# 02_Arduino_Headers.net
KiCad netlist of a schematic drawn in Altium Designer
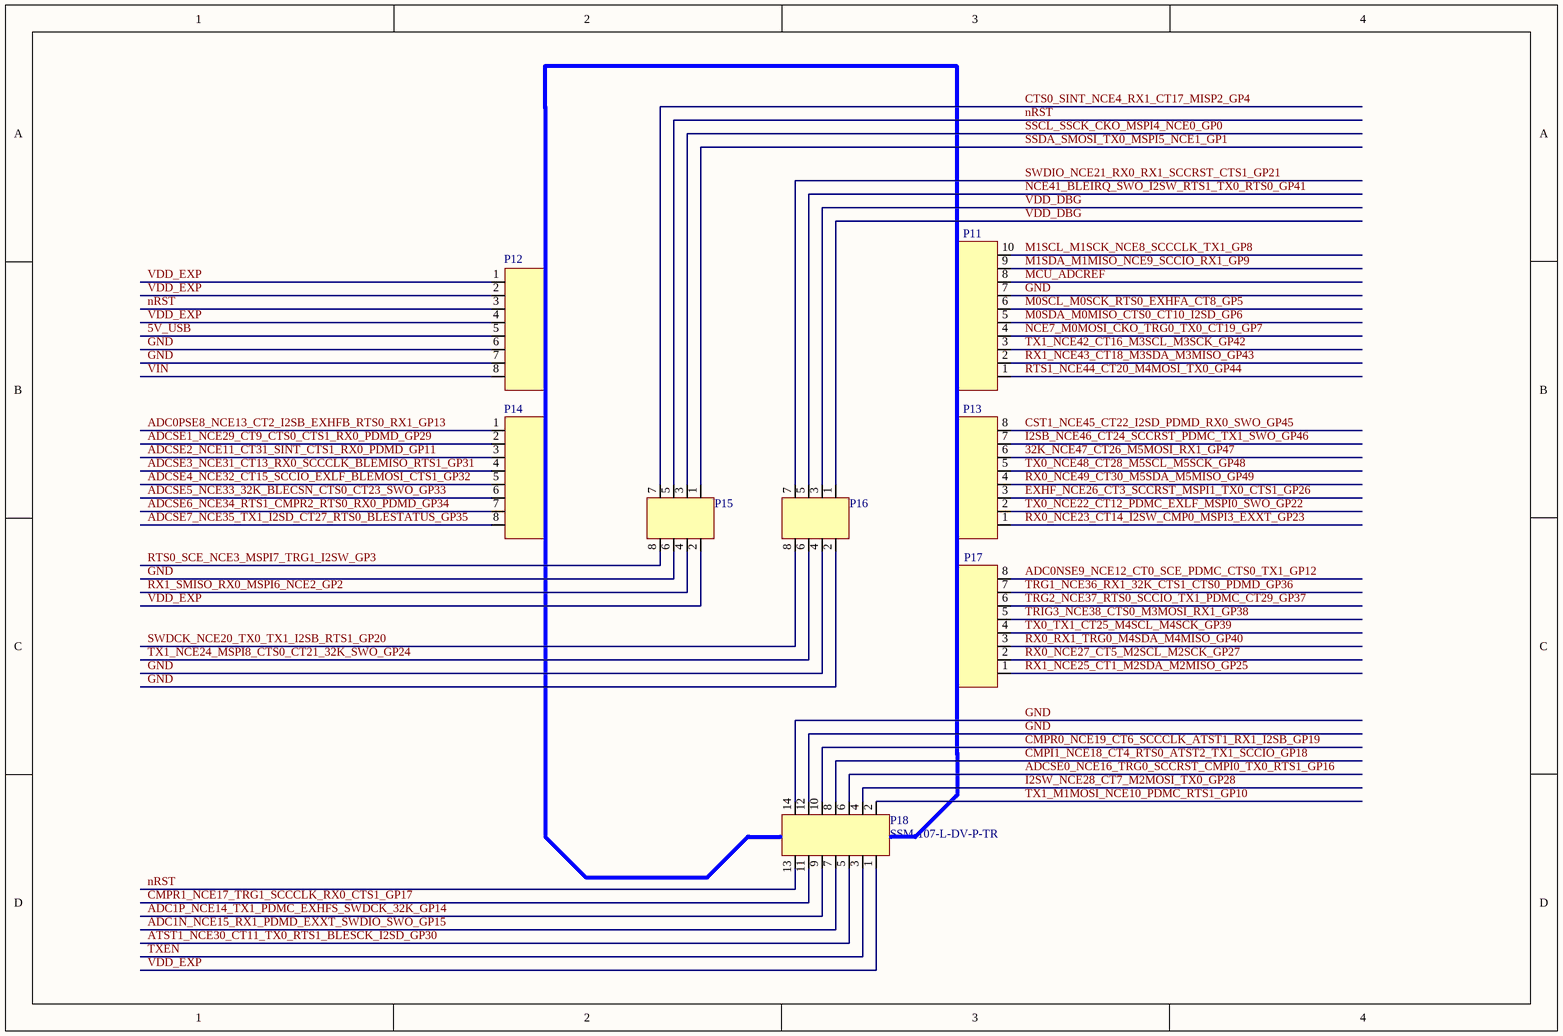
[diagram p0: [02]Arduino Headers.SchDoc]

(export (version "E")
  (design (tool "Eeschema 10.0.6"))
  (components
    (comp (ref "P11")
      (value "SSM-110-L-SV-P-TR")
      (footprint "SSM-110-L-SV-TR")
      (description "10 Position Receptacle, Pass Through Connector 2.54mm Gold SMD")
      (libsource (lib "Connector") (part "SSM-110-L-SV-P-TR"))
    )
    (comp (ref "P12")
      (value "SSM-108-L-SV-P-TR")
      (footprint "SSM-108-L-SV-TR")
      (description "8 Position Receptacle, Pass Through Connector 2.54mm Gold SMD")
      (libsource (lib "") (part "SSM-108-L-SV-P-TR_1"))
    )
    (comp (ref "P13")
      (value "SSM-108-L-SV-P-TR")
      (footprint "SSM-108-L-SV-TR")
      (description "8 Position Receptacle, Pass Through Connector 2.54mm Gold SMD")
      (libsource (lib "Connector") (part "SSM-108-L-SV-P-TR"))
    )
    (comp (ref "P14")
      (value "SSM-108-L-SV-P-TR")
      (footprint "SSM-108-L-SV-TR")
      (description "8 Position Receptacle, Pass Through Connector 2.54mm Gold SMD")
      (libsource (lib "") (part "SSM-108-L-SV-P-TR_1"))
    )
    (comp (ref "P15")
      (value "TSM-104-04-F-DV-P-TR")
      (footprint "TSM-104-04-F-DV-TR")
      (description "8 Positions Header, 2 Row,Gold, Unshrouded Connector 2.54mm SMD")
      (libsource (lib "Connector") (part "TSM-104-04-F-DV-P-TR"))
    )
    (comp (ref "P16")
      (value "TSM-104-04-F-DV-P-TR")
      (footprint "TSM-104-04-F-DV-TR")
      (description "8 Positions Header, 2 Row,Gold, Unshrouded Connector 2.54mm SMD")
      (libsource (lib "Connector") (part "TSM-104-04-F-DV-P-TR"))
    )
    (comp (ref "P17")
      (value "SSM-108-L-SV-P-TR")
      (footprint "SSM-108-L-SV-TR")
      (description "8 Position Receptacle, Pass Through Connector 2.54mm Gold SMD")
      (libsource (lib "Connector") (part "SSM-108-L-SV-P-TR"))
    )
    (comp (ref "P18")
      (value "SSM-107-L-DV-P-TR")
      (footprint "SSM-107-L-DV-TR")
      (description "14 Positions Socket Strip, Double Row Vertical 2,54mm SMD")
      (libsource (lib "Connector") (part "SSM-107-L-DV-P-TR"))
    )
  )
  (nets
    (net (code "1") (name "/5V_USB") (class "Default")
      (node (ref "P12") (pin "5") (pinfunction "5_5") (pintype "passive"))
    )
    (net (code "2") (name "/32K_NCE47_CT26_M5MOSI_RX1_GP47") (class "Default")
      (node (ref "P13") (pin "6") (pinfunction "6_6") (pintype "passive"))
    )
    (net (code "3") (name "/ADC0NSE9_NCE12_CT0_SCE_PDMC_CTS0_TX1_GP12") (class "Default")
      (node (ref "P17") (pin "8") (pinfunction "8_8") (pintype "passive"))
    )
    (net (code "4") (name "/ADC0PSE8_NCE13_CT2_I2SB_EXHFB_RTS0_RX1_GP13") (class "Default")
      (node (ref "P14") (pin "1") (pinfunction "1_1") (pintype "passive"))
    )
    (net (code "5") (name "/ADC1N_NCE15_RX1_PDMD_EXXT_SWDIO_SWO_GP15") (class "Default")
      (node (ref "P18") (pin "7") (pinfunction "7_7") (pintype "passive"))
    )
    (net (code "6") (name "/ADC1P_NCE14_TX1_PDMC_EXHFS_SWDCK_32K_GP14") (class "Default")
      (node (ref "P18") (pin "9") (pinfunction "9_9") (pintype "passive"))
    )
    (net (code "7") (name "/ADCSE0_NCE16_TRG0_SCCRST_CMPI0_TX0_RTS1_GP16") (class "Default")
      (node (ref "P18") (pin "6") (pinfunction "6_6") (pintype "passive"))
    )
    (net (code "8") (name "/ADCSE1_NCE29_CT9_CTS0_CTS1_RX0_PDMD_GP29") (class "Default")
      (node (ref "P14") (pin "2") (pinfunction "2_2") (pintype "passive"))
    )
    (net (code "9") (name "/ADCSE2_NCE11_CT31_SINT_CTS1_RX0_PDMD_GP11") (class "Default")
      (node (ref "P14") (pin "3") (pinfunction "3_3") (pintype "passive"))
    )
    (net (code "10") (name "/ADCSE3_NCE31_CT13_RX0_SCCCLK_BLEMISO_RTS1_GP31") (class "Default")
      (node (ref "P14") (pin "4") (pinfunction "4_4") (pintype "passive"))
    )
    (net (code "11") (name "/ADCSE4_NCE32_CT15_SCCIO_EXLF_BLEMOSI_CTS1_GP32") (class "Default")
      (node (ref "P14") (pin "5") (pinfunction "5_5") (pintype "passive"))
    )
    (net (code "12") (name "/ADCSE5_NCE33_32K_BLECSN_CTS0_CT23_SWO_GP33") (class "Default")
      (node (ref "P14") (pin "6") (pinfunction "6_6") (pintype "passive"))
    )
    (net (code "13") (name "/ADCSE6_NCE34_RTS1_CMPR2_RTS0_RX0_PDMD_GP34") (class "Default")
      (node (ref "P14") (pin "7") (pinfunction "7_7") (pintype "passive"))
    )
    (net (code "14") (name "/ADCSE7_NCE35_TX1_I2SD_CT27_RTS0_BLESTATUS_GP35") (class "Default")
      (node (ref "P14") (pin "8") (pinfunction "8_8") (pintype "passive"))
    )
    (net (code "15") (name "/ATST1_NCE30_CT11_TX0_RTS1_BLESCK_I2SD_GP30") (class "Default")
      (node (ref "P18") (pin "5") (pinfunction "5_5") (pintype "passive"))
    )
    (net (code "16") (name "/CMPI1_NCE18_CT4_RTS0_ATST2_TX1_SCCIO_GP18") (class "Default")
      (node (ref "P18") (pin "8") (pinfunction "8_8") (pintype "passive"))
    )
    (net (code "17") (name "/CMPR0_NCE19_CT6_SCCCLK_ATST1_RX1_I2SB_GP19") (class "Default")
      (node (ref "P18") (pin "10") (pinfunction "10_10") (pintype "passive"))
    )
    (net (code "18") (name "/CMPR1_NCE17_TRG1_SCCCLK_RX0_CTS1_GP17") (class "Default")
      (node (ref "P18") (pin "11") (pinfunction "11_11") (pintype "passive"))
    )
    (net (code "19") (name "/CST1_NCE45_CT22_I2SD_PDMD_RX0_SWO_GP45") (class "Default")
      (node (ref "P13") (pin "8") (pinfunction "8_8") (pintype "passive"))
    )
    (net (code "20") (name "/CTS0_SINT_NCE4_RX1_CT17_MISP2_GP4") (class "Default")
      (node (ref "P15") (pin "7") (pinfunction "7_7") (pintype "passive"))
    )
    (net (code "21") (name "/EXHF_NCE26_CT3_SCCRST_MSPI1_TX0_CTS1_GP26") (class "Default")
      (node (ref "P13") (pin "3") (pinfunction "3_3") (pintype "passive"))
    )
    (net (code "22") (name "/GND") (class "Default")
      (node (ref "P11") (pin "7") (pinfunction "7_7") (pintype "passive"))
      (node (ref "P12") (pin "6") (pinfunction "6_6") (pintype "passive"))
      (node (ref "P12") (pin "7") (pinfunction "7_7") (pintype "passive"))
      (node (ref "P15") (pin "6") (pinfunction "6_6") (pintype "passive"))
      (node (ref "P16") (pin "2") (pinfunction "2_2") (pintype "passive"))
      (node (ref "P16") (pin "4") (pinfunction "4_4") (pintype "passive"))
      (node (ref "P18") (pin "12") (pinfunction "12_12") (pintype "passive"))
      (node (ref "P18") (pin "14") (pinfunction "14_14") (pintype "passive"))
    )
    (net (code "23") (name "/I2SB_NCE46_CT24_SCCRST_PDMC_TX1_SWO_GP46") (class "Default")
      (node (ref "P13") (pin "7") (pinfunction "7_7") (pintype "passive"))
    )
    (net (code "24") (name "/I2SW_NCE28_CT7_M2MOSI_TX0_GP28") (class "Default")
      (node (ref "P18") (pin "4") (pinfunction "4_4") (pintype "passive"))
    )
    (net (code "25") (name "/M0SCL_M0SCK_RTS0_EXHFA_CT8_GP5") (class "Default")
      (node (ref "P11") (pin "6") (pinfunction "6_6") (pintype "passive"))
    )
    (net (code "26") (name "/M0SDA_M0MISO_CTS0_CT10_I2SD_GP6") (class "Default")
      (node (ref "P11") (pin "5") (pinfunction "5_5") (pintype "passive"))
    )
    (net (code "27") (name "/M1SCL_M1SCK_NCE8_SCCCLK_TX1_GP8") (class "Default")
      (node (ref "P11") (pin "10") (pinfunction "10_10") (pintype "passive"))
    )
    (net (code "28") (name "/M1SDA_M1MISO_NCE9_SCCIO_RX1_GP9") (class "Default")
      (node (ref "P11") (pin "9") (pinfunction "9_9") (pintype "passive"))
    )
    (net (code "29") (name "/MCU_ADCREF") (class "Default")
      (node (ref "P11") (pin "8") (pinfunction "8_8") (pintype "passive"))
    )
    (net (code "30") (name "/NCE7_M0MOSI_CKO_TRG0_TX0_CT19_GP7") (class "Default")
      (node (ref "P11") (pin "4") (pinfunction "4_4") (pintype "passive"))
    )
    (net (code "31") (name "/NCE41_BLEIRQ_SWO_I2SW_RTS1_TX0_RTS0_GP41") (class "Default")
      (node (ref "P16") (pin "5") (pinfunction "5_5") (pintype "passive"))
    )
    (net (code "32") (name "/RTS0_SCE_NCE3_MSPI7_TRG1_I2SW_GP3") (class "Default")
      (node (ref "P15") (pin "8") (pinfunction "8_8") (pintype "passive"))
    )
    (net (code "33") (name "/RTS1_NCE44_CT20_M4MOSI_TX0_GP44") (class "Default")
      (node (ref "P11") (pin "1") (pinfunction "1_1") (pintype "passive"))
    )
    (net (code "34") (name "/RX0_NCE23_CT14_I2SW_CMP0_MSPI3_EXXT_GP23") (class "Default")
      (node (ref "P13") (pin "1") (pinfunction "1_1") (pintype "passive"))
    )
    (net (code "35") (name "/RX0_NCE27_CT5_M2SCL_M2SCK_GP27") (class "Default")
      (node (ref "P17") (pin "2") (pinfunction "2_2") (pintype "passive"))
    )
    (net (code "36") (name "/RX0_NCE49_CT30_M5SDA_M5MISO_GP49") (class "Default")
      (node (ref "P13") (pin "4") (pinfunction "4_4") (pintype "passive"))
    )
    (net (code "37") (name "/RX0_RX1_TRG0_M4SDA_M4MISO_GP40") (class "Default")
      (node (ref "P17") (pin "3") (pinfunction "3_3") (pintype "passive"))
    )
    (net (code "38") (name "/RX1_NCE25_CT1_M2SDA_M2MISO_GP25") (class "Default")
      (node (ref "P17") (pin "1") (pinfunction "1_1") (pintype "passive"))
    )
    (net (code "39") (name "/RX1_NCE43_CT18_M3SDA_M3MISO_GP43") (class "Default")
      (node (ref "P11") (pin "2") (pinfunction "2_2") (pintype "passive"))
    )
    (net (code "40") (name "/RX1_SMISO_RX0_MSPI6_NCE2_GP2") (class "Default")
      (node (ref "P15") (pin "4") (pinfunction "4_4") (pintype "passive"))
    )
    (net (code "41") (name "/SSCL_SSCK_CKO_MSPI4_NCE0_GP0") (class "Default")
      (node (ref "P15") (pin "3") (pinfunction "3_3") (pintype "passive"))
    )
    (net (code "42") (name "/SSDA_SMOSI_TX0_MSPI5_NCE1_GP1") (class "Default")
      (node (ref "P15") (pin "1") (pinfunction "1_1") (pintype "passive"))
    )
    (net (code "43") (name "/SWDCK_NCE20_TX0_TX1_I2SB_RTS1_GP20") (class "Default")
      (node (ref "P16") (pin "8") (pinfunction "8_8") (pintype "passive"))
    )
    (net (code "44") (name "/SWDIO_NCE21_RX0_RX1_SCCRST_CTS1_GP21") (class "Default")
      (node (ref "P16") (pin "7") (pinfunction "7_7") (pintype "passive"))
    )
    (net (code "45") (name "/TRG1_NCE36_RX1_32K_CTS1_CTS0_PDMD_GP36") (class "Default")
      (node (ref "P17") (pin "7") (pinfunction "7_7") (pintype "passive"))
    )
    (net (code "46") (name "/TRG2_NCE37_RTS0_SCCIO_TX1_PDMC_CT29_GP37") (class "Default")
      (node (ref "P17") (pin "6") (pinfunction "6_6") (pintype "passive"))
    )
    (net (code "47") (name "/TRIG3_NCE38_CTS0_M3MOSI_RX1_GP38") (class "Default")
      (node (ref "P17") (pin "5") (pinfunction "5_5") (pintype "passive"))
    )
    (net (code "48") (name "/TX0_NCE22_CT12_PDMC_EXLF_MSPI0_SWO_GP22") (class "Default")
      (node (ref "P13") (pin "2") (pinfunction "2_2") (pintype "passive"))
    )
    (net (code "49") (name "/TX0_NCE48_CT28_M5SCL_M5SCK_GP48") (class "Default")
      (node (ref "P13") (pin "5") (pinfunction "5_5") (pintype "passive"))
    )
    (net (code "50") (name "/TX0_TX1_CT25_M4SCL_M4SCK_GP39") (class "Default")
      (node (ref "P17") (pin "4") (pinfunction "4_4") (pintype "passive"))
    )
    (net (code "51") (name "/TX1_M1MOSI_NCE10_PDMC_RTS1_GP10") (class "Default")
      (node (ref "P18") (pin "2") (pinfunction "2_2") (pintype "passive"))
    )
    (net (code "52") (name "/TX1_NCE24_MSPI8_CTS0_CT21_32K_SWO_GP24") (class "Default")
      (node (ref "P16") (pin "6") (pinfunction "6_6") (pintype "passive"))
    )
    (net (code "53") (name "/TX1_NCE42_CT16_M3SCL_M3SCK_GP42") (class "Default")
      (node (ref "P11") (pin "3") (pinfunction "3_3") (pintype "passive"))
    )
    (net (code "54") (name "/TXEN") (class "Default")
      (node (ref "P18") (pin "3") (pinfunction "3_3") (pintype "passive"))
    )
    (net (code "55") (name "/VDD_DBG") (class "Default")
      (node (ref "P16") (pin "1") (pinfunction "1_1") (pintype "passive"))
      (node (ref "P16") (pin "3") (pinfunction "3_3") (pintype "passive"))
    )
    (net (code "56") (name "/VDD_EXP") (class "Default")
      (node (ref "P12") (pin "1") (pinfunction "1_1") (pintype "passive"))
      (node (ref "P12") (pin "2") (pinfunction "2_2") (pintype "passive"))
      (node (ref "P12") (pin "4") (pinfunction "4_4") (pintype "passive"))
      (node (ref "P15") (pin "2") (pinfunction "2_2") (pintype "passive"))
      (node (ref "P18") (pin "1") (pinfunction "1_1") (pintype "passive"))
    )
    (net (code "57") (name "/VIN") (class "Default")
      (node (ref "P12") (pin "8") (pinfunction "8_8") (pintype "passive"))
    )
    (net (code "58") (name "/nRST") (class "Default")
      (node (ref "P12") (pin "3") (pinfunction "3_3") (pintype "passive"))
      (node (ref "P15") (pin "5") (pinfunction "5_5") (pintype "passive"))
      (node (ref "P18") (pin "13") (pinfunction "13_13") (pintype "passive"))
    )
  )
)
